# SNC8600A.net
KiCad netlist of a schematic drawn in Altium Designer
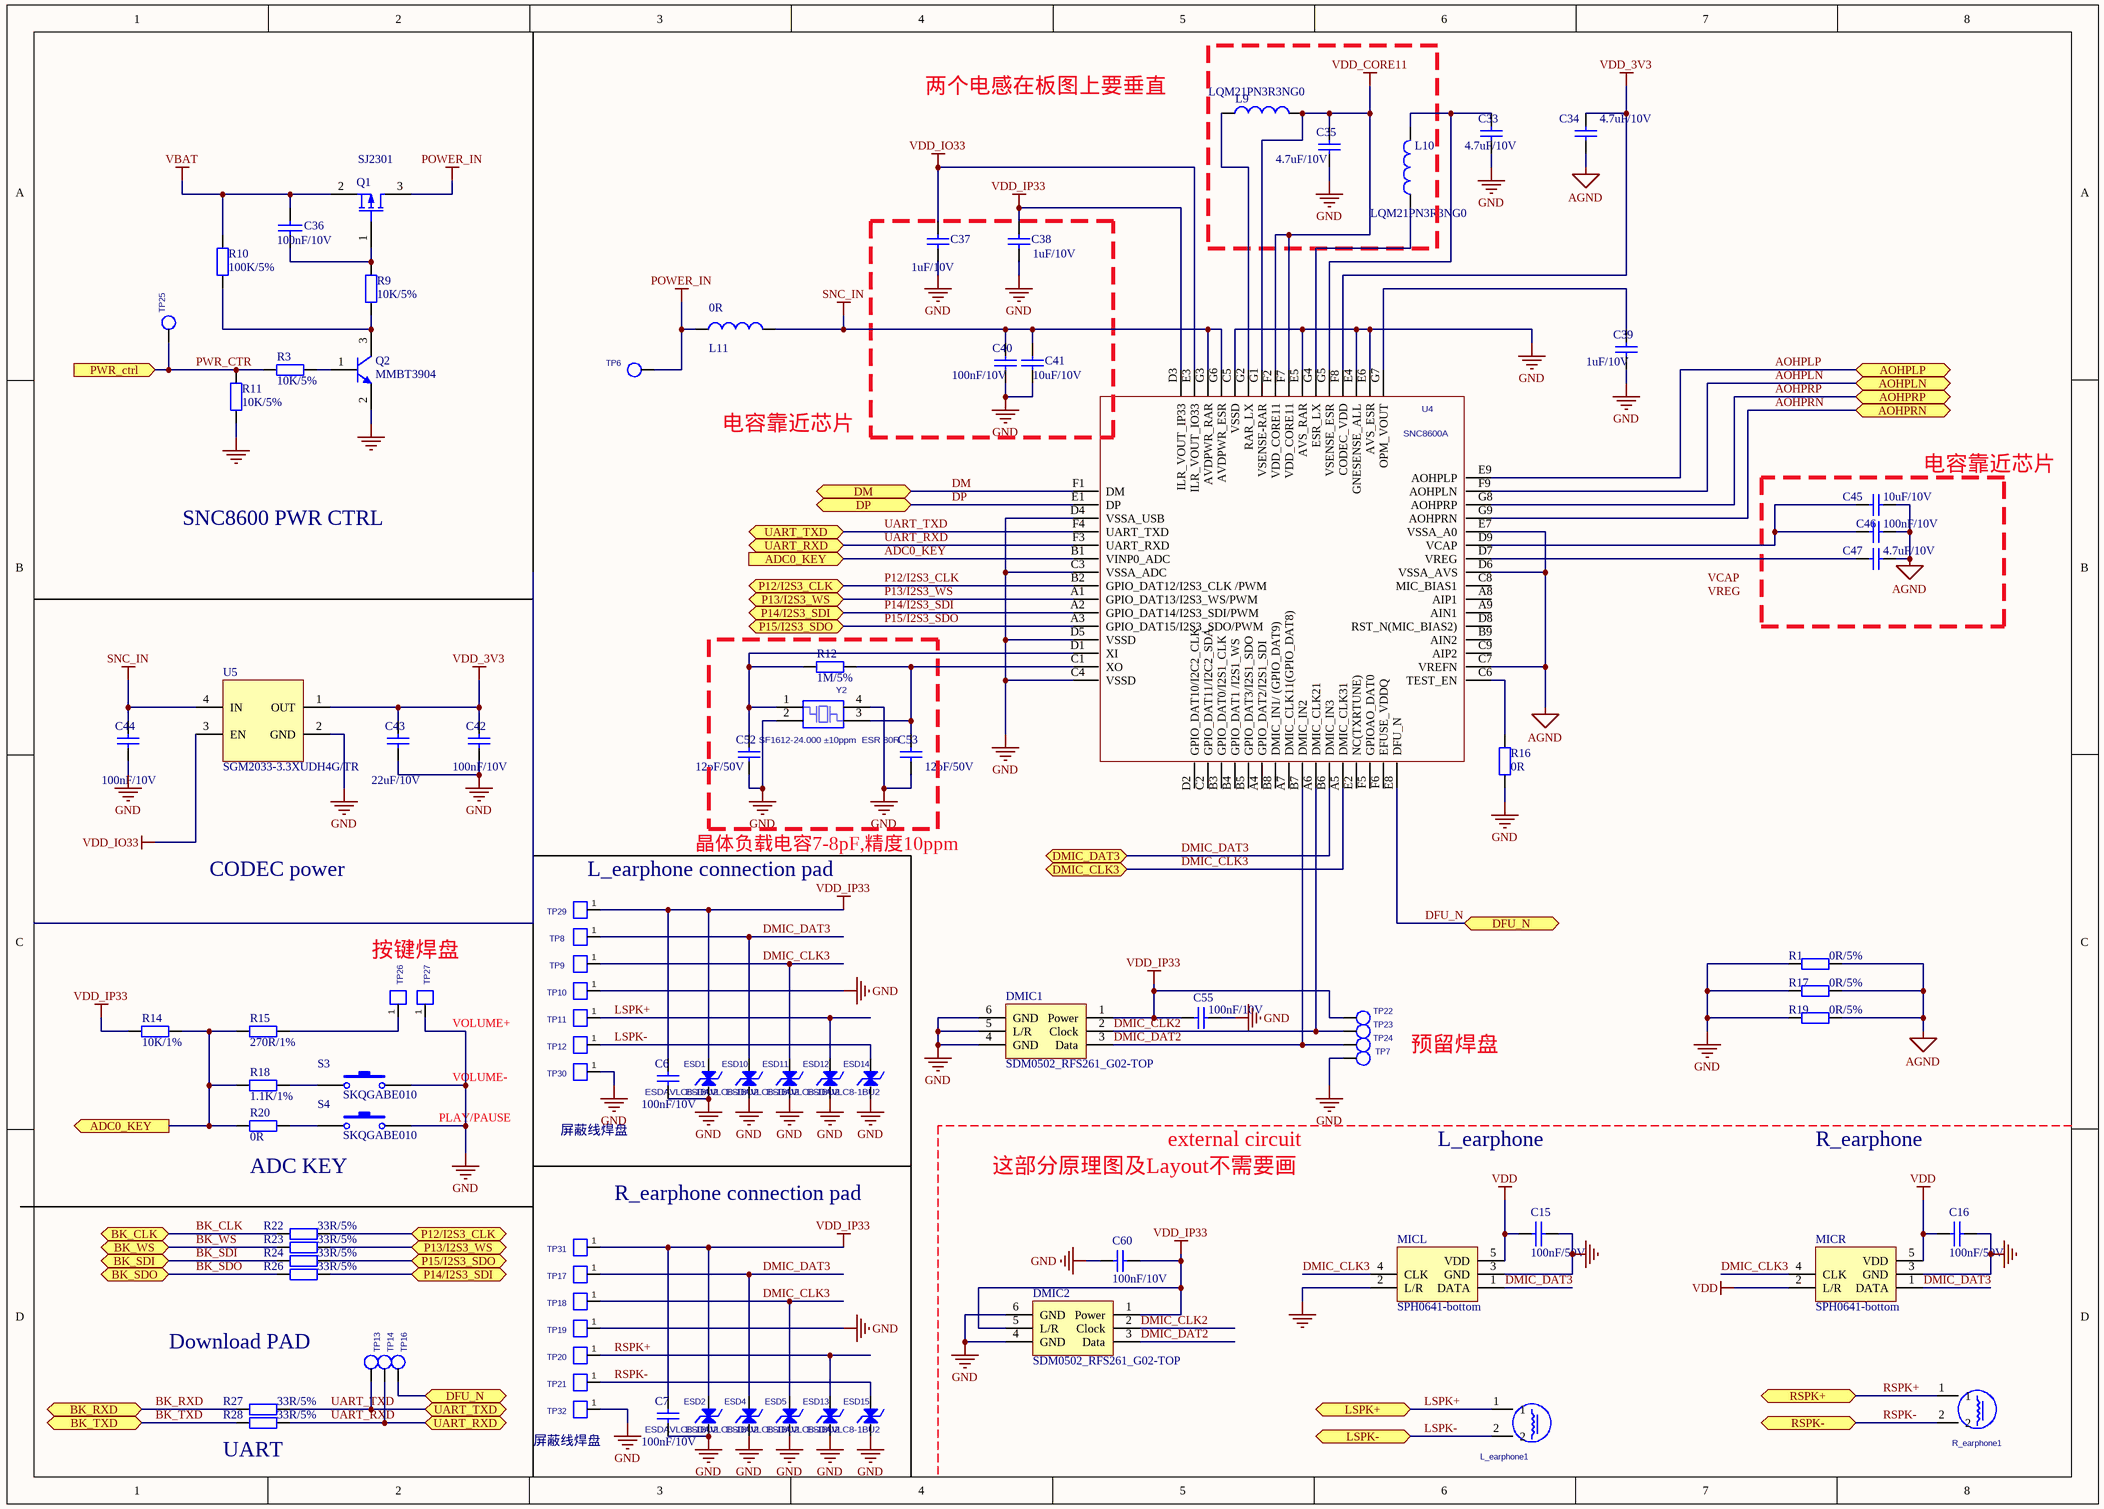
[diagram p0: SNC8600A.SchDoc]

(export (version "E")
  (design (tool "Eeschema 10.0.6"))
  (components
    (comp (ref "C6")
      (value "100nF/10V")
      (footprint "0201")
      (description "Capacitor (Semiconductor SIM Model)")
      (fields (field (name "PUBLISHER") "Altium Limited"))
      (libsource (lib "Miscellaneous Devices") (part "Cap Semi"))
    )
    (comp (ref "C7")
      (value "100nF/10V")
      (footprint "0201")
      (description "Capacitor (Semiconductor SIM Model)")
      (fields (field (name "PUBLISHER") "Altium Limited"))
      (libsource (lib "Miscellaneous Devices") (part "Cap Semi"))
    )
    (comp (ref "C15")
      (value "100nF/50V")
      (footprint "0201")
      (description "Capacitor")
      (libsource (lib "MIC1") (part "CAP-0201"))
    )
    (comp (ref "C16")
      (value "100nF/50V")
      (footprint "0201")
      (description "Capacitor")
      (libsource (lib "MIC1") (part "CAP-0201"))
    )
    (comp (ref "C33")
      (value "4.7uF/10V")
      (footprint "C0402")
      (description "Capacitor (Semiconductor SIM Model)")
      (fields (field (name "PUBLISHER") "Altium Limited"))
      (libsource (lib "Miscellaneous Devices") (part "Cap Semi"))
    )
    (comp (ref "C34")
      (value "4.7uF/10V")
      (footprint "C0402")
      (description "Capacitor (Semiconductor SIM Model)")
      (fields (field (name "PUBLISHER") "Altium Limited"))
      (libsource (lib "Miscellaneous Devices") (part "Cap Semi"))
    )
    (comp (ref "C35")
      (value "4.7uF/10V")
      (footprint "C0402")
      (description "Capacitor (Semiconductor SIM Model)")
      (fields (field (name "PUBLISHER") "Altium Limited"))
      (libsource (lib "Miscellaneous Devices") (part "Cap Semi"))
    )
    (comp (ref "C36")
      (value "100nF/10V")
      (footprint "0201")
      (description "Capacitor")
      (libsource (lib "*") (part "CAP"))
    )
    (comp (ref "C37")
      (value "1uF/10V")
      (footprint "0201")
      (description "Capacitor (Semiconductor SIM Model)")
      (fields (field (name "PUBLISHER") "Altium Limited"))
      (libsource (lib "Miscellaneous Devices") (part "Cap Semi"))
    )
    (comp (ref "C38")
      (value "1uF/10V")
      (footprint "0201")
      (description "Capacitor (Semiconductor SIM Model)")
      (fields (field (name "PUBLISHER") "Altium Limited"))
      (libsource (lib "Miscellaneous Devices") (part "Cap Semi"))
    )
    (comp (ref "C39")
      (value "1uF/10V")
      (footprint "0201")
      (description "Capacitor (Semiconductor SIM Model)")
      (fields (field (name "PUBLISHER") "Altium Limited"))
      (libsource (lib "Miscellaneous Devices") (part "Cap Semi"))
    )
    (comp (ref "C40")
      (value "100nF/10V")
      (footprint "0201")
      (description "Capacitor (Semiconductor SIM Model)")
      (fields (field (name "PUBLISHER") "Altium Limited"))
      (libsource (lib "Miscellaneous Devices") (part "Cap Semi"))
    )
    (comp (ref "C41")
      (value "10uF/10V")
      (footprint "C0402")
      (description "Capacitor (Semiconductor SIM Model)")
      (fields (field (name "PUBLISHER") "Altium Limited"))
      (libsource (lib "Miscellaneous Devices") (part "Cap Semi"))
    )
    (comp (ref "C42")
      (value "100nF/10V")
      (footprint "0201")
      (description "Capacitor (Semiconductor SIM Model)")
      (fields (field (name "PUBLISHER") "Altium Limited"))
      (libsource (lib "Miscellaneous Devices") (part "Cap Semi"))
    )
    (comp (ref "C43")
      (value "22uF/10V")
      (footprint "C0402")
      (description "Capacitor (Semiconductor SIM Model)")
      (fields (field (name "PUBLISHER") "Altium Limited"))
      (libsource (lib "Miscellaneous Devices") (part "Cap Semi"))
    )
    (comp (ref "C44")
      (value "100nF/10V")
      (footprint "0201")
      (description "Capacitor (Semiconductor SIM Model)")
      (fields (field (name "PUBLISHER") "Altium Limited"))
      (libsource (lib "Miscellaneous Devices") (part "Cap Semi"))
    )
    (comp (ref "C45")
      (value "10uF/10V")
      (footprint "C0402")
      (description "Capacitor (Semiconductor SIM Model)")
      (fields (field (name "PUBLISHER") "Altium Limited"))
      (libsource (lib "Miscellaneous Devices") (part "Cap Semi"))
    )
    (comp (ref "C46")
      (value "100nF/10V")
      (footprint "0201")
      (description "Capacitor (Semiconductor SIM Model)")
      (fields (field (name "PUBLISHER") "Altium Limited"))
      (libsource (lib "Miscellaneous Devices") (part "Cap Semi"))
    )
    (comp (ref "C47")
      (value "4.7uF/10V")
      (footprint "C0402")
      (description "Capacitor (Semiconductor SIM Model)")
      (fields (field (name "PUBLISHER") "Altium Limited"))
      (libsource (lib "Miscellaneous Devices") (part "Cap Semi"))
    )
    (comp (ref "C52")
      (value "12pF/50V")
      (footprint "0201")
      (description "Capacitor (Semiconductor SIM Model)")
      (fields (field (name "PUBLISHER") "Altium Limited"))
      (libsource (lib "Miscellaneous Devices") (part "Cap Semi"))
    )
    (comp (ref "C53")
      (value "12pF/50V")
      (footprint "0201")
      (description "Capacitor (Semiconductor SIM Model)")
      (fields (field (name "PUBLISHER") "Altium Limited"))
      (libsource (lib "Miscellaneous Devices") (part "Cap Semi"))
    )
    (comp (ref "C55")
      (value "100nF/10V")
      (footprint "0201")
      (description "Capacitor (Semiconductor SIM Model)")
      (fields (field (name "PUBLISHER") "Altium Limited"))
      (libsource (lib "Miscellaneous Devices") (part "Cap Semi"))
    )
    (comp (ref "C60")
      (value "100nF/10V")
      (footprint "0201")
      (description "Capacitor (Semiconductor SIM Model)")
      (fields (field (name "PUBLISHER") "Altium Limited"))
      (libsource (lib "Miscellaneous Devices") (part "Cap Semi"))
    )
    (comp (ref "DMIC1")
      (value "SDM0502_RFS261_G02-TOP")
      (footprint "3526_TOP")
      (libsource (lib "EVB-SCH-LCD-202003152") (part "3526-TOP"))
    )
    (comp (ref "DMIC2")
      (value "SDM0502_RFS261_G02-TOP")
      (footprint "3526_TOP")
      (libsource (lib "EVB-SCH-LCD-202003152") (part "3526-TOP"))
    )
    (comp (ref "ESD1")
      (value "ESDAVLC8-1BU2")
      (footprint "0201")
      (libsource (lib "EVB-SCH-LCD-202003152") (part "ESD"))
    )
    (comp (ref "ESD2")
      (value "ESDAVLC8-1BU2")
      (footprint "0201")
      (libsource (lib "EVB-SCH-LCD-202003152") (part "ESD"))
    )
    (comp (ref "ESD4")
      (value "ESDAVLC8-1BU2")
      (footprint "0201")
      (libsource (lib "EVB-SCH-LCD-202003152") (part "ESD"))
    )
    (comp (ref "ESD5")
      (value "ESDAVLC8-1BU2")
      (footprint "0201")
      (libsource (lib "EVB-SCH-LCD-202003152") (part "ESD"))
    )
    (comp (ref "ESD10")
      (value "ESDAVLC8-1BU2")
      (footprint "0201")
      (libsource (lib "EVB-SCH-LCD-202003152") (part "ESD"))
    )
    (comp (ref "ESD11")
      (value "ESDAVLC8-1BU2")
      (footprint "0201")
      (libsource (lib "EVB-SCH-LCD-202003152") (part "ESD"))
    )
    (comp (ref "ESD12")
      (value "ESDAVLC8-1BU2")
      (footprint "0201")
      (libsource (lib "EVB-SCH-LCD-202003152") (part "ESD"))
    )
    (comp (ref "ESD13")
      (value "ESDAVLC8-1BU2")
      (footprint "0201")
      (libsource (lib "EVB-SCH-LCD-202003152") (part "ESD"))
    )
    (comp (ref "ESD14")
      (value "ESDAVLC8-1BU2")
      (footprint "0201")
      (libsource (lib "EVB-SCH-LCD-202003152") (part "ESD"))
    )
    (comp (ref "ESD15")
      (value "ESDAVLC8-1BU2")
      (footprint "0201")
      (libsource (lib "EVB-SCH-LCD-202003152") (part "ESD"))
    )
    (comp (ref "L9")
      (value "LQM21PN3R3NG0")
      (footprint "L0805")
      (description "Inductor")
      (fields (field (name "PUBLISHER") "Altium Limited"))
      (libsource (lib "Miscellaneous Devices") (part "Inductor"))
    )
    (comp (ref "L10")
      (value "LQM21PN3R3NG0")
      (footprint "L0805")
      (description "Inductor")
      (fields (field (name "PUBLISHER") "Altium Limited"))
      (libsource (lib "Miscellaneous Devices") (part "Inductor"))
    )
    (comp (ref "L11")
      (value "0R")
      (footprint "0201")
      (description "Inductor")
      (fields (field (name "PUBLISHER") "Altium Limited"))
      (libsource (lib "Miscellaneous Devices") (part "Inductor"))
    )
    (comp (ref "L_earphone1")
      (value "TS1")
      (footprint "2PIN-2.54")
      (libsource (lib "EVB-SCH-LCD-202003152") (part "TS1"))
    )
    (comp (ref "MICL")
      (value "SPH0641-bottom")
      (footprint "SPH_3526")
      (description "MEMS MICPHONE")
      (fields (field (name "PUBLISHER") "Altium Limited"))
      (libsource (lib "MIC1") (part "SPH0641"))
    )
    (comp (ref "MICR")
      (value "SPH0641-bottom")
      (footprint "SPH_3526")
      (description "MEMS MICPHONE")
      (fields (field (name "PUBLISHER") "Altium Limited"))
      (libsource (lib "MIC1") (part "SPH0641"))
    )
    (comp (ref "Q1")
      (value "SJ2301")
      (footprint "SOT23_3407")
      (description "P-Channel MOSFET")
      (fields (field (name "PUBLISHER") "Altium Limited"))
      (libsource (lib "Miscellaneous Devices") (part "MOSFET-P"))
    )
    (comp (ref "Q2")
      (value "MMBT3904")
      (footprint "SOT23")
      (description "NPN General Purpose Amplifier")
      (fields (field (name "PUBLISHER") "Altium Limited"))
      (libsource (lib "Miscellaneous Devices") (part "2N3904"))
    )
    (comp (ref "R1")
      (value "0R/5%")
      (footprint "0201")
      (description "Resistor")
      (fields (field (name "PUBLISHER") "Altium Limited"))
      (libsource (lib "Miscellaneous Devices") (part "Res2"))
    )
    (comp (ref "R3")
      (value "10K/5%")
      (footprint "0201")
      (description "Resistor")
      (fields (field (name "PUBLISHER") "Altium Limited"))
      (libsource (lib "") (part "Res2_2"))
    )
    (comp (ref "R9")
      (value "10K/5%")
      (footprint "0201")
      (description "Resistor")
      (fields (field (name "PUBLISHER") "Altium Limited"))
      (libsource (lib "") (part "Res2_1"))
    )
    (comp (ref "R10")
      (value "100K/5%")
      (footprint "0201")
      (description "Resistor")
      (fields (field (name "PUBLISHER") "Altium Limited"))
      (libsource (lib "") (part "Res2_1"))
    )
    (comp (ref "R11")
      (value "10K/5%")
      (footprint "0201")
      (description "Resistor")
      (fields (field (name "PUBLISHER") "Altium Limited"))
      (libsource (lib "") (part "Res2_1"))
    )
    (comp (ref "R12")
      (value "1M/5%")
      (footprint "0201")
      (description "Resistor")
      (fields (field (name "PUBLISHER") "Altium Limited"))
      (libsource (lib "Miscellaneous Devices") (part "Res2"))
    )
    (comp (ref "R14")
      (value "10K/1%")
      (footprint "0201")
      (description "Resistor")
      (fields (field (name "PUBLISHER") "Altium Limited"))
      (libsource (lib "Miscellaneous Devices") (part "Res2"))
    )
    (comp (ref "R15")
      (value "270R/1%")
      (footprint "0201")
      (description "Resistor")
      (fields (field (name "PUBLISHER") "Altium Limited"))
      (libsource (lib "Miscellaneous Devices") (part "Res2"))
    )
    (comp (ref "R16")
      (value "0R")
      (footprint "0201")
      (description "Resistor")
      (fields (field (name "PUBLISHER") "Altium Limited"))
      (libsource (lib "") (part "Res2_1"))
    )
    (comp (ref "R17")
      (value "0R/5%")
      (footprint "0201")
      (description "Resistor")
      (fields (field (name "PUBLISHER") "Altium Limited"))
      (libsource (lib "Miscellaneous Devices") (part "Res2"))
    )
    (comp (ref "R18")
      (value "1.1K/1%")
      (footprint "0201")
      (description "Resistor")
      (fields (field (name "PUBLISHER") "Altium Limited"))
      (libsource (lib "Miscellaneous Devices") (part "Res2"))
    )
    (comp (ref "R19")
      (value "0R/5%")
      (footprint "0201")
      (description "Resistor")
      (fields (field (name "PUBLISHER") "Altium Limited"))
      (libsource (lib "Miscellaneous Devices") (part "Res2"))
    )
    (comp (ref "R20")
      (value "0R")
      (footprint "0201")
      (description "Resistor")
      (fields (field (name "PUBLISHER") "Altium Limited"))
      (libsource (lib "Miscellaneous Devices") (part "Res2"))
    )
    (comp (ref "R22")
      (value "33R/5%")
      (footprint "0201")
      (description "Resistor")
      (fields (field (name "PUBLISHER") "Altium Limited"))
      (libsource (lib "Miscellaneous Devices") (part "Res2"))
    )
    (comp (ref "R23")
      (value "33R/5%")
      (footprint "0201")
      (description "Resistor")
      (fields (field (name "PUBLISHER") "Altium Limited"))
      (libsource (lib "Miscellaneous Devices") (part "Res2"))
    )
    (comp (ref "R24")
      (value "33R/5%")
      (footprint "0201")
      (description "Resistor")
      (fields (field (name "PUBLISHER") "Altium Limited"))
      (libsource (lib "Miscellaneous Devices") (part "Res2"))
    )
    (comp (ref "R26")
      (value "33R/5%")
      (footprint "0201")
      (description "Resistor")
      (fields (field (name "PUBLISHER") "Altium Limited"))
      (libsource (lib "Miscellaneous Devices") (part "Res2"))
    )
    (comp (ref "R27")
      (value "33R/5%")
      (footprint "0201")
      (description "Resistor")
      (fields (field (name "PUBLISHER") "Altium Limited"))
      (libsource (lib "Miscellaneous Devices") (part "Res2"))
    )
    (comp (ref "R28")
      (value "33R/5%")
      (footprint "0201")
      (description "Resistor")
      (fields (field (name "PUBLISHER") "Altium Limited"))
      (libsource (lib "Miscellaneous Devices") (part "Res2"))
    )
    (comp (ref "R_earphone1")
      (value "TS1")
      (footprint "2PIN-2.54")
      (libsource (lib "EVB-SCH-LCD-202003152") (part "TS1"))
    )
    (comp (ref "S3")
      (value "SKQGABE010")
      (footprint "TD-302060")
      (description "Switch")
      (fields (field (name "PUBLISHER") "Altium Limited"))
      (libsource (lib "Miscellaneous Devices") (part "SW-PB"))
    )
    (comp (ref "S4")
      (value "SKQGABE010")
      (footprint "TD-302060")
      (description "Switch")
      (fields (field (name "PUBLISHER") "Altium Limited"))
      (libsource (lib "Miscellaneous Devices") (part "SW-PB"))
    )
    (comp (ref "TP6")
      (value "TP1")
      (footprint "TP1-1MM")
      (libsource (lib "EVB-SCH-LCD-202003152") (part "TP1"))
    )
    (comp (ref "TP7")
      (value "TP1")
      (footprint "TP1-1MM")
      (libsource (lib "EVB-SCH-LCD-202003152") (part "TP1"))
    )
    (comp (ref "TP8")
      (value "TP")
      (footprint "TP1-1MM")
      (libsource (lib "EVB-SCH-LCD-202003152") (part "TP"))
    )
    (comp (ref "TP9")
      (value "TP")
      (footprint "TP1-1MM")
      (libsource (lib "EVB-SCH-LCD-202003152") (part "TP"))
    )
    (comp (ref "TP10")
      (value "TP")
      (footprint "TP1-1MM")
      (libsource (lib "EVB-SCH-LCD-202003152") (part "TP"))
    )
    (comp (ref "TP11")
      (value "TP")
      (footprint "TP1-1MM")
      (libsource (lib "EVB-SCH-LCD-202003152") (part "TP"))
    )
    (comp (ref "TP12")
      (value "TP")
      (footprint "TP1-1MM")
      (libsource (lib "EVB-SCH-LCD-202003152") (part "TP"))
    )
    (comp (ref "TP13")
      (value "TP1")
      (footprint "TP1-1MM")
      (libsource (lib "EVB-SCH-LCD-202003152") (part "TP1"))
    )
    (comp (ref "TP14")
      (value "TP1")
      (footprint "TP1-1MM")
      (libsource (lib "EVB-SCH-LCD-202003152") (part "TP1"))
    )
    (comp (ref "TP16")
      (value "TP1")
      (footprint "TP1-1MM")
      (libsource (lib "EVB-SCH-LCD-202003152") (part "TP1"))
    )
    (comp (ref "TP17")
      (value "TP")
      (footprint "TP1-1MM")
      (libsource (lib "EVB-SCH-LCD-202003152") (part "TP"))
    )
    (comp (ref "TP18")
      (value "TP")
      (footprint "TP1-1MM")
      (libsource (lib "EVB-SCH-LCD-202003152") (part "TP"))
    )
    (comp (ref "TP19")
      (value "TP")
      (footprint "TP1-1MM")
      (libsource (lib "EVB-SCH-LCD-202003152") (part "TP"))
    )
    (comp (ref "TP20")
      (value "TP")
      (footprint "TP1-1MM")
      (libsource (lib "EVB-SCH-LCD-202003152") (part "TP"))
    )
    (comp (ref "TP21")
      (value "TP")
      (footprint "TP1-1MM")
      (libsource (lib "EVB-SCH-LCD-202003152") (part "TP"))
    )
    (comp (ref "TP22")
      (value "TP1")
      (footprint "TP1-1MM")
      (libsource (lib "EVB-SCH-LCD-202003152") (part "TP1"))
    )
    (comp (ref "TP23")
      (value "TP1")
      (footprint "TP1-1MM")
      (libsource (lib "EVB-SCH-LCD-202003152") (part "TP1"))
    )
    (comp (ref "TP24")
      (value "TP1")
      (footprint "TP1-1MM")
      (libsource (lib "EVB-SCH-LCD-202003152") (part "TP1"))
    )
    (comp (ref "TP25")
      (value "TP1")
      (footprint "TP1-1MM")
      (libsource (lib "EVB-SCH-LCD-202003152") (part "TP1"))
    )
    (comp (ref "TP26")
      (value "TP")
      (footprint "TP1-1MM")
      (libsource (lib "EVB-SCH-LCD-202003152") (part "TP"))
    )
    (comp (ref "TP27")
      (value "TP")
      (footprint "TP1-1MM")
      (libsource (lib "EVB-SCH-LCD-202003152") (part "TP"))
    )
    (comp (ref "TP29")
      (value "TP")
      (footprint "TP1-1MM")
      (libsource (lib "EVB-SCH-LCD-202003152") (part "TP"))
    )
    (comp (ref "TP30")
      (value "TP")
      (footprint "TP1-1MM")
      (libsource (lib "EVB-SCH-LCD-202003152") (part "TP"))
    )
    (comp (ref "TP31")
      (value "TP")
      (footprint "TP1-1MM")
      (libsource (lib "EVB-SCH-LCD-202003152") (part "TP"))
    )
    (comp (ref "TP32")
      (value "TP")
      (footprint "TP1-1MM")
      (libsource (lib "EVB-SCH-LCD-202003152") (part "TP"))
    )
    (comp (ref "U4")
      (value "SNC8600A")
      (footprint "BGA63C50P9X7_500X350X100")
      (libsource (lib "EVB-SCH-LCD-202003152") (part "SNC8600A"))
    )
    (comp (ref "U5")
      (value "SGM2033-3.3XUDH4G/TR")
      (footprint "UTDFN-1X1-4AL")
      (libsource (lib "EVB-SCH-LCD-202003152") (part "SGM2033"))
    )
    (comp (ref "Y2")
      (value "SF1612-24.000 ±10ppm  ESR 80R")
      (footprint "SF1612")
      (fields (field (name "Comment") "SF1612"))
      (libsource (lib "EVB-SCH-LCD-202003152") (part "SF1612"))
    )
  )
  (nets
    (net (code "1") (name "/ADC0_KEY") (class "Default")
      (node (ref "R14") (pin "1") (pinfunction "1_1") (pintype "passive"))
      (node (ref "R15") (pin "2") (pinfunction "2_2") (pintype "passive"))
      (node (ref "R18") (pin "2") (pinfunction "2_2") (pintype "passive"))
      (node (ref "R20") (pin "2") (pinfunction "2_2") (pintype "passive"))
      (node (ref "U4") (pin "B1") (pinfunction "VINP0_ADC_B1") (pintype "passive"))
    )
    (net (code "2") (name "/AOHPLN") (class "Default")
      (node (ref "U4") (pin "F9") (pinfunction "AOHPLN_F9") (pintype "passive"))
    )
    (net (code "3") (name "/AOHPLP") (class "Default")
      (node (ref "U4") (pin "E9") (pinfunction "AOHPLP_E9") (pintype "passive"))
    )
    (net (code "4") (name "/AOHPRN") (class "Default")
      (node (ref "U4") (pin "G9") (pinfunction "AOHPRN_G9") (pintype "passive"))
    )
    (net (code "5") (name "/AOHPRP") (class "Default")
      (node (ref "U4") (pin "G8") (pinfunction "AOHPRP_G8") (pintype "passive"))
    )
    (net (code "6") (name "/BK_CLK") (class "Default")
      (node (ref "R22") (pin "2") (pinfunction "2_2") (pintype "passive"))
    )
    (net (code "7") (name "/BK_RXD") (class "Default")
      (node (ref "R27") (pin "2") (pinfunction "2_2") (pintype "passive"))
    )
    (net (code "8") (name "/BK_SDI") (class "Default")
      (node (ref "R24") (pin "2") (pinfunction "2_2") (pintype "passive"))
    )
    (net (code "9") (name "/BK_SDO") (class "Default")
      (node (ref "R26") (pin "2") (pinfunction "2_2") (pintype "passive"))
    )
    (net (code "10") (name "/BK_TXD") (class "Default")
      (node (ref "R28") (pin "2") (pinfunction "2_2") (pintype "passive"))
    )
    (net (code "11") (name "/BK_WS") (class "Default")
      (node (ref "R23") (pin "2") (pinfunction "2_2") (pintype "passive"))
    )
    (net (code "12") (name "/DFU_N") (class "Default")
      (node (ref "TP16") (pin "1") (pinfunction "1_1") (pintype "passive"))
      (node (ref "U4") (pin "E8") (pinfunction "DFU_N_E8") (pintype "passive"))
    )
    (net (code "13") (name "/DM") (class "Default")
      (node (ref "U4") (pin "F1") (pinfunction "DM_F1") (pintype "passive"))
    )
    (net (code "14") (name "/DMIC_CLK2") (class "Default")
      (node (ref "DMIC1") (pin "2") (pinfunction "Clock_2") (pintype "passive"))
      (node (ref "DMIC2") (pin "2") (pinfunction "Clock_2") (pintype "passive"))
      (node (ref "TP23") (pin "1") (pinfunction "1_1") (pintype "passive"))
      (node (ref "U4") (pin "A6") (pinfunction "DMIC_CLK21_A6") (pintype "passive"))
    )
    (net (code "15") (name "/DMIC_CLK3") (class "Default")
      (node (ref "ESD11") (pin "1") (pinfunction "1_1") (pintype "passive"))
      (node (ref "ESD5") (pin "1") (pinfunction "1_1") (pintype "passive"))
      (node (ref "MICL") (pin "4") (pinfunction "CLK_4") (pintype "power_in"))
      (node (ref "MICR") (pin "4") (pinfunction "CLK_4") (pintype "power_in"))
      (node (ref "TP18") (pin "1") (pinfunction "1_1") (pintype "passive"))
      (node (ref "TP9") (pin "1") (pinfunction "1_1") (pintype "passive"))
      (node (ref "U4") (pin "A5") (pinfunction "DMIC_CLK31_A5") (pintype "passive"))
    )
    (net (code "16") (name "/DMIC_DAT2") (class "Default")
      (node (ref "DMIC1") (pin "3") (pinfunction "Data_3") (pintype "passive"))
      (node (ref "DMIC2") (pin "3") (pinfunction "Data_3") (pintype "passive"))
      (node (ref "TP24") (pin "1") (pinfunction "1_1") (pintype "passive"))
      (node (ref "U4") (pin "B7") (pinfunction "DMIC_IN2_B7") (pintype "passive"))
    )
    (net (code "17") (name "/DMIC_DAT3") (class "Default")
      (node (ref "ESD10") (pin "1") (pinfunction "1_1") (pintype "passive"))
      (node (ref "ESD4") (pin "1") (pinfunction "1_1") (pintype "passive"))
      (node (ref "MICL") (pin "1") (pinfunction "DATA_1") (pintype "passive"))
      (node (ref "MICR") (pin "1") (pinfunction "DATA_1") (pintype "passive"))
      (node (ref "TP17") (pin "1") (pinfunction "1_1") (pintype "passive"))
      (node (ref "TP8") (pin "1") (pinfunction "1_1") (pintype "passive"))
      (node (ref "U4") (pin "B6") (pinfunction "DMIC_IN3_B6") (pintype "passive"))
    )
    (net (code "18") (name "/DP") (class "Default")
      (node (ref "U4") (pin "E1") (pinfunction "DP_E1") (pintype "passive"))
    )
    (net (code "19") (name "/LSPK+") (class "Default")
      (node (ref "ESD12") (pin "1") (pinfunction "1_1") (pintype "passive"))
      (node (ref "L_earphone1") (pin "1") (pinfunction "1_1") (pintype "passive"))
      (node (ref "TP11") (pin "1") (pinfunction "1_1") (pintype "passive"))
    )
    (net (code "20") (name "/LSPK-") (class "Default")
      (node (ref "ESD14") (pin "1") (pinfunction "1_1") (pintype "passive"))
      (node (ref "L_earphone1") (pin "2") (pinfunction "2_2") (pintype "passive"))
      (node (ref "TP12") (pin "1") (pinfunction "1_1") (pintype "passive"))
    )
    (net (code "21") (name "/P12{slash}I2S3_CLK") (class "Default")
      (node (ref "R22") (pin "1") (pinfunction "1_1") (pintype "passive"))
      (node (ref "U4") (pin "B2") (pinfunction "GPIO_DAT12/I2S3_CLK_/PWM_B2") (pintype "passive"))
    )
    (net (code "22") (name "/P13{slash}I2S3_WS") (class "Default")
      (node (ref "R23") (pin "1") (pinfunction "1_1") (pintype "passive"))
      (node (ref "U4") (pin "A1") (pinfunction "GPIO_DAT13/I2S3_WS/PWM_A1") (pintype "passive"))
    )
    (net (code "23") (name "/P14{slash}I2S3_SDI") (class "Default")
      (node (ref "R26") (pin "1") (pinfunction "1_1") (pintype "passive"))
      (node (ref "U4") (pin "A2") (pinfunction "GPIO_DAT14/I2S3_SDI/PWM_A2") (pintype "passive"))
    )
    (net (code "24") (name "/P15{slash}I2S3_SDO") (class "Default")
      (node (ref "R24") (pin "1") (pinfunction "1_1") (pintype "passive"))
      (node (ref "U4") (pin "A3") (pinfunction "GPIO_DAT15/I2S3_SDO/PWM_A3") (pintype "passive"))
    )
    (net (code "25") (name "/PWR_CTR") (class "Default")
      (node (ref "R11") (pin "1") (pinfunction "1_1") (pintype "passive"))
      (node (ref "R3") (pin "1") (pinfunction "1_1") (pintype "passive"))
      (node (ref "TP25") (pin "1") (pinfunction "1_1") (pintype "passive"))
    )
    (net (code "26") (name "/RSPK+") (class "Default")
      (node (ref "ESD13") (pin "1") (pinfunction "1_1") (pintype "passive"))
      (node (ref "R_earphone1") (pin "1") (pinfunction "1_1") (pintype "passive"))
      (node (ref "TP20") (pin "1") (pinfunction "1_1") (pintype "passive"))
    )
    (net (code "27") (name "/RSPK-") (class "Default")
      (node (ref "ESD15") (pin "1") (pinfunction "1_1") (pintype "passive"))
      (node (ref "R_earphone1") (pin "2") (pinfunction "2_2") (pintype "passive"))
      (node (ref "TP21") (pin "1") (pinfunction "1_1") (pintype "passive"))
    )
    (net (code "28") (name "/UART_RXD") (class "Default")
      (node (ref "R28") (pin "1") (pinfunction "1_1") (pintype "passive"))
      (node (ref "TP14") (pin "1") (pinfunction "1_1") (pintype "passive"))
      (node (ref "U4") (pin "F3") (pinfunction "UART_RXD_F3") (pintype "passive"))
    )
    (net (code "29") (name "/UART_TXD") (class "Default")
      (node (ref "R27") (pin "1") (pinfunction "1_1") (pintype "passive"))
      (node (ref "TP13") (pin "1") (pinfunction "1_1") (pintype "passive"))
      (node (ref "U4") (pin "F4") (pinfunction "UART_TXD_F4") (pintype "passive"))
    )
    (net (code "32") (name "AGND") (class "Default")
      (node (ref "C34") (pin "1") (pinfunction "1_1") (pintype "passive"))
      (node (ref "C45") (pin "1") (pinfunction "1_1") (pintype "passive"))
      (node (ref "C46") (pin "1") (pinfunction "1_1") (pintype "passive"))
      (node (ref "C47") (pin "1") (pinfunction "1_1") (pintype "passive"))
      (node (ref "R1") (pin "1") (pinfunction "1_1") (pintype "passive"))
      (node (ref "R17") (pin "1") (pinfunction "1_1") (pintype "passive"))
      (node (ref "R19") (pin "1") (pinfunction "1_1") (pintype "passive"))
      (node (ref "U4") (pin "C7") (pinfunction "VREFN_C7") (pintype "passive"))
      (node (ref "U4") (pin "D6") (pinfunction "VSSA_AVS_D6") (pintype "passive"))
      (node (ref "U4") (pin "E7") (pinfunction "VSSA_A0_E7") (pintype "passive"))
    )
    (net (code "33") (name "GND") (class "Default")
      (node (ref "C15") (pin "1") (pinfunction "1_1") (pintype "passive"))
      (node (ref "C16") (pin "1") (pinfunction "1_1") (pintype "passive"))
      (node (ref "C33") (pin "1") (pinfunction "1_1") (pintype "passive"))
      (node (ref "C35") (pin "1") (pinfunction "1_1") (pintype "passive"))
      (node (ref "C37") (pin "1") (pinfunction "1_1") (pintype "passive"))
      (node (ref "C38") (pin "1") (pinfunction "1_1") (pintype "passive"))
      (node (ref "C39") (pin "1") (pinfunction "1_1") (pintype "passive"))
      (node (ref "C40") (pin "1") (pinfunction "1_1") (pintype "passive"))
      (node (ref "C41") (pin "1") (pinfunction "1_1") (pintype "passive"))
      (node (ref "C42") (pin "1") (pinfunction "1_1") (pintype "passive"))
      (node (ref "C43") (pin "1") (pinfunction "1_1") (pintype "passive"))
      (node (ref "C44") (pin "1") (pinfunction "1_1") (pintype "passive"))
      (node (ref "C52") (pin "1") (pinfunction "1_1") (pintype "passive"))
      (node (ref "C53") (pin "1") (pinfunction "1_1") (pintype "passive"))
      (node (ref "C55") (pin "1") (pinfunction "1_1") (pintype "passive"))
      (node (ref "C6") (pin "1") (pinfunction "1_1") (pintype "passive"))
      (node (ref "C60") (pin "1") (pinfunction "1_1") (pintype "passive"))
      (node (ref "C7") (pin "1") (pinfunction "1_1") (pintype "passive"))
      (node (ref "DMIC1") (pin "4") (pinfunction "GND_4") (pintype "passive"))
      (node (ref "DMIC1") (pin "5") (pinfunction "L/R_5") (pintype "passive"))
      (node (ref "DMIC1") (pin "6") (pinfunction "GND_6") (pintype "passive"))
      (node (ref "DMIC2") (pin "4") (pinfunction "GND_4") (pintype "passive"))
      (node (ref "DMIC2") (pin "6") (pinfunction "GND_6") (pintype "passive"))
      (node (ref "ESD1") (pin "2") (pinfunction "2_2") (pintype "passive"))
      (node (ref "ESD10") (pin "2") (pinfunction "2_2") (pintype "passive"))
      (node (ref "ESD11") (pin "2") (pinfunction "2_2") (pintype "passive"))
      (node (ref "ESD12") (pin "2") (pinfunction "2_2") (pintype "passive"))
      (node (ref "ESD13") (pin "2") (pinfunction "2_2") (pintype "passive"))
      (node (ref "ESD14") (pin "2") (pinfunction "2_2") (pintype "passive"))
      (node (ref "ESD15") (pin "2") (pinfunction "2_2") (pintype "passive"))
      (node (ref "ESD2") (pin "2") (pinfunction "2_2") (pintype "passive"))
      (node (ref "ESD4") (pin "2") (pinfunction "2_2") (pintype "passive"))
      (node (ref "ESD5") (pin "2") (pinfunction "2_2") (pintype "passive"))
      (node (ref "MICL") (pin "2") (pinfunction "L/R_2") (pintype "passive"))
      (node (ref "MICL") (pin "3") (pinfunction "GND_3") (pintype "power_in"))
      (node (ref "MICR") (pin "3") (pinfunction "GND_3") (pintype "power_in"))
      (node (ref "Q2") (pin "2") (pinfunction "E_2") (pintype "passive"))
      (node (ref "R1") (pin "2") (pinfunction "2_2") (pintype "passive"))
      (node (ref "R11") (pin "2") (pinfunction "2_2") (pintype "passive"))
      (node (ref "R16") (pin "2") (pinfunction "2_2") (pintype "passive"))
      (node (ref "R17") (pin "2") (pinfunction "2_2") (pintype "passive"))
      (node (ref "R19") (pin "2") (pinfunction "2_2") (pintype "passive"))
      (node (ref "S3") (pin "1") (pinfunction "1_1") (pintype "passive"))
      (node (ref "S4") (pin "1") (pinfunction "1_1") (pintype "passive"))
      (node (ref "TP10") (pin "1") (pinfunction "1_1") (pintype "passive"))
      (node (ref "TP19") (pin "1") (pinfunction "1_1") (pintype "passive"))
      (node (ref "TP27") (pin "1") (pinfunction "1_1") (pintype "passive"))
      (node (ref "TP30") (pin "1") (pinfunction "1_1") (pintype "passive"))
      (node (ref "TP32") (pin "1") (pinfunction "1_1") (pintype "passive"))
      (node (ref "TP7") (pin "1") (pinfunction "1_1") (pintype "passive"))
      (node (ref "U4") (pin "C3") (pinfunction "VSSA_ADC_C3") (pintype "passive"))
      (node (ref "U4") (pin "C4") (pinfunction "VSSD_C4") (pintype "passive"))
      (node (ref "U4") (pin "C5") (pinfunction "VSSD_C5") (pintype "passive"))
      (node (ref "U4") (pin "D4") (pinfunction "VSSA_USB_D4") (pintype "passive"))
      (node (ref "U4") (pin "D5") (pinfunction "VSSD_D5") (pintype "passive"))
      (node (ref "U4") (pin "E4") (pinfunction "GNESENSE_ALL_E4") (pintype "passive"))
      (node (ref "U4") (pin "E5") (pinfunction "AVS_RAR_E5") (pintype "passive"))
      (node (ref "U4") (pin "E6") (pinfunction "AVS_ESR_E6") (pintype "passive"))
      (node (ref "U5") (pin "2") (pinfunction "GND_2") (pintype "passive"))
      (node (ref "Y2") (pin "2") (pinfunction "2_2") (pintype "passive"))
      (node (ref "Y2") (pin "4") (pinfunction "4_4") (pintype "passive"))
    )
    (net (code "34") (name "Net-(Q1-G)") (class "Default")
      (node (ref "C36") (pin "1") (pinfunction "1_1") (pintype "passive"))
      (node (ref "Q1") (pin "1") (pinfunction "G_1") (pintype "passive"))
      (node (ref "R9") (pin "1") (pinfunction "1_1") (pintype "passive"))
    )
    (net (code "35") (name "Net-(Q2-B)") (class "Default")
      (node (ref "Q2") (pin "1") (pinfunction "B_1") (pintype "passive"))
      (node (ref "R3") (pin "2") (pinfunction "2_2") (pintype "passive"))
    )
    (net (code "36") (name "Net-(Q2-C)") (class "Default")
      (node (ref "Q2") (pin "3") (pinfunction "C_3") (pintype "passive"))
      (node (ref "R10") (pin "2") (pinfunction "2_2") (pintype "passive"))
      (node (ref "R9") (pin "2") (pinfunction "2_2") (pintype "passive"))
    )
    (net (code "37") (name "Net-(R15-Pad1)") (class "Default")
      (node (ref "R15") (pin "1") (pinfunction "1_1") (pintype "passive"))
      (node (ref "TP26") (pin "1") (pinfunction "1_1") (pintype "passive"))
    )
    (net (code "38") (name "Net-(R18-Pad1)") (class "Default")
      (node (ref "R18") (pin "1") (pinfunction "1_1") (pintype "passive"))
      (node (ref "S3") (pin "2") (pinfunction "2_2") (pintype "passive"))
    )
    (net (code "39") (name "Net-(R20-Pad1)") (class "Default")
      (node (ref "R20") (pin "1") (pinfunction "1_1") (pintype "passive"))
      (node (ref "S4") (pin "2") (pinfunction "2_2") (pintype "passive"))
    )
    (net (code "40") (name "Net-(U4-ESR_LX)") (class "Default")
      (node (ref "L10") (pin "1") (pinfunction "1_1") (pintype "passive"))
      (node (ref "U4") (pin "G4") (pinfunction "ESR_LX_G4") (pintype "passive"))
    )
    (net (code "41") (name "Net-(U4-OPM_VOUT)") (class "Default")
      (node (ref "C39") (pin "2") (pinfunction "2_2") (pintype "passive"))
      (node (ref "U4") (pin "G7") (pinfunction "OPM_VOUT_G7") (pintype "passive"))
    )
    (net (code "42") (name "Net-(U4-RAR_LX)") (class "Default")
      (node (ref "L9") (pin "1") (pinfunction "1_1") (pintype "passive"))
      (node (ref "U4") (pin "G2") (pinfunction "RAR_LX_G2") (pintype "passive"))
    )
    (net (code "43") (name "Net-(U4-TEST_EN)") (class "Default")
      (node (ref "R16") (pin "1") (pinfunction "1_1") (pintype "passive"))
      (node (ref "U4") (pin "C6") (pinfunction "TEST_EN_C6") (pintype "passive"))
    )
    (net (code "44") (name "Net-(U4-VCAP)") (class "Default")
      (node (ref "C45") (pin "2") (pinfunction "2_2") (pintype "passive"))
      (node (ref "C46") (pin "2") (pinfunction "2_2") (pintype "passive"))
      (node (ref "U4") (pin "D9") (pinfunction "VCAP_D9") (pintype "passive"))
    )
    (net (code "45") (name "Net-(U4-VREG)") (class "Default")
      (node (ref "C47") (pin "2") (pinfunction "2_2") (pintype "passive"))
      (node (ref "U4") (pin "D7") (pinfunction "VREG_D7") (pintype "passive"))
    )
    (net (code "46") (name "Net-(U4-VSENSE_ESR)") (class "Default")
      (node (ref "C33") (pin "2") (pinfunction "2_2") (pintype "passive"))
      (node (ref "L10") (pin "2") (pinfunction "2_2") (pintype "passive"))
      (node (ref "U4") (pin "G5") (pinfunction "VSENSE_ESR_G5") (pintype "passive"))
    )
    (net (code "47") (name "Net-(U4-XI)") (class "Default")
      (node (ref "C52") (pin "2") (pinfunction "2_2") (pintype "passive"))
      (node (ref "R12") (pin "2") (pinfunction "2_2") (pintype "passive"))
      (node (ref "U4") (pin "D1") (pinfunction "XI_D1") (pintype "passive"))
      (node (ref "Y2") (pin "1") (pinfunction "1_1") (pintype "passive"))
    )
    (net (code "48") (name "Net-(U4-XO)") (class "Default")
      (node (ref "C53") (pin "2") (pinfunction "2_2") (pintype "passive"))
      (node (ref "R12") (pin "1") (pinfunction "1_1") (pintype "passive"))
      (node (ref "U4") (pin "C1") (pinfunction "XO_C1") (pintype "passive"))
      (node (ref "Y2") (pin "3") (pinfunction "3_3") (pintype "passive"))
    )
    (net (code "49") (name "POWER_IN") (class "Default")
      (node (ref "L11") (pin "1") (pinfunction "1_1") (pintype "passive"))
      (node (ref "Q1") (pin "3") (pinfunction "D_3") (pintype "passive"))
      (node (ref "TP6") (pin "1") (pinfunction "1_1") (pintype "passive"))
    )
    (net (code "50") (name "SNC_IN") (class "Default")
      (node (ref "C40") (pin "2") (pinfunction "2_2") (pintype "passive"))
      (node (ref "C41") (pin "2") (pinfunction "2_2") (pintype "passive"))
      (node (ref "C44") (pin "2") (pinfunction "2_2") (pintype "passive"))
      (node (ref "L11") (pin "2") (pinfunction "2_2") (pintype "passive"))
      (node (ref "U4") (pin "G3") (pinfunction "AVDPWR_RAR_G3") (pintype "passive"))
      (node (ref "U4") (pin "G6") (pinfunction "AVDPWR_ESR_G6") (pintype "passive"))
      (node (ref "U5") (pin "4") (pinfunction "IN_4") (pintype "passive"))
    )
    (net (code "51") (name "VBAT") (class "Default")
      (node (ref "C36") (pin "2") (pinfunction "2_2") (pintype "passive"))
      (node (ref "Q1") (pin "2") (pinfunction "S_2") (pintype "passive"))
      (node (ref "R10") (pin "1") (pinfunction "1_1") (pintype "passive"))
    )
    (net (code "52") (name "VDD") (class "Default")
      (node (ref "C15") (pin "2") (pinfunction "2_2") (pintype "passive"))
      (node (ref "C16") (pin "2") (pinfunction "2_2") (pintype "passive"))
      (node (ref "MICL") (pin "5") (pinfunction "VDD_5") (pintype "power_in"))
      (node (ref "MICR") (pin "2") (pinfunction "L/R_2") (pintype "passive"))
      (node (ref "MICR") (pin "5") (pinfunction "VDD_5") (pintype "power_in"))
    )
    (net (code "53") (name "VDD_3V3") (class "Default")
      (node (ref "C34") (pin "2") (pinfunction "2_2") (pintype "passive"))
      (node (ref "C42") (pin "2") (pinfunction "2_2") (pintype "passive"))
      (node (ref "C43") (pin "2") (pinfunction "2_2") (pintype "passive"))
      (node (ref "U4") (pin "F8") (pinfunction "CODEC_VDD_F8") (pintype "passive"))
      (node (ref "U5") (pin "1") (pinfunction "OUT_1") (pintype "passive"))
    )
    (net (code "54") (name "VDD_CORE11") (class "Default")
      (node (ref "C35") (pin "2") (pinfunction "2_2") (pintype "passive"))
      (node (ref "L9") (pin "2") (pinfunction "2_2") (pintype "passive"))
      (node (ref "U4") (pin "F2") (pinfunction "VDD_CORE11_F2") (pintype "passive"))
      (node (ref "U4") (pin "F7") (pinfunction "VDD_CORE11_F7") (pintype "passive"))
      (node (ref "U4") (pin "G1") (pinfunction "VSENSE-RAR_G1") (pintype "passive"))
    )
    (net (code "55") (name "VDD_IO33") (class "Default")
      (node (ref "C37") (pin "2") (pinfunction "2_2") (pintype "passive"))
      (node (ref "U4") (pin "E3") (pinfunction "ILR_VOUT_IO33_E3") (pintype "passive"))
      (node (ref "U5") (pin "3") (pinfunction "EN_3") (pintype "passive"))
    )
    (net (code "56") (name "VDD_IP33") (class "Default")
      (node (ref "C38") (pin "2") (pinfunction "2_2") (pintype "passive"))
      (node (ref "C55") (pin "2") (pinfunction "2_2") (pintype "passive"))
      (node (ref "C6") (pin "2") (pinfunction "2_2") (pintype "passive"))
      (node (ref "C60") (pin "2") (pinfunction "2_2") (pintype "passive"))
      (node (ref "C7") (pin "2") (pinfunction "2_2") (pintype "passive"))
      (node (ref "DMIC1") (pin "1") (pinfunction "Power_1") (pintype "passive"))
      (node (ref "DMIC2") (pin "1") (pinfunction "Power_1") (pintype "passive"))
      (node (ref "DMIC2") (pin "5") (pinfunction "L/R_5") (pintype "passive"))
      (node (ref "ESD1") (pin "1") (pinfunction "1_1") (pintype "passive"))
      (node (ref "ESD2") (pin "1") (pinfunction "1_1") (pintype "passive"))
      (node (ref "R14") (pin "2") (pinfunction "2_2") (pintype "passive"))
      (node (ref "TP22") (pin "1") (pinfunction "1_1") (pintype "passive"))
      (node (ref "TP29") (pin "1") (pinfunction "1_1") (pintype "passive"))
      (node (ref "TP31") (pin "1") (pinfunction "1_1") (pintype "passive"))
      (node (ref "U4") (pin "D3") (pinfunction "ILR_VOUT_IP33_D3") (pintype "passive"))
    )
    (net (code "57") (name "unconnected-(U4-AIN1-PadA9)") (class "Default")
      (node (ref "U4") (pin "A9") (pinfunction "AIN1_A9") (pintype "passive"))
    )
    (net (code "58") (name "unconnected-(U4-AIN2-PadB9)") (class "Default")
      (node (ref "U4") (pin "B9") (pinfunction "AIN2_B9") (pintype "passive"))
    )
    (net (code "59") (name "unconnected-(U4-AIP1-PadA8)") (class "Default")
      (node (ref "U4") (pin "A8") (pinfunction "AIP1_A8") (pintype "passive"))
    )
    (net (code "60") (name "unconnected-(U4-AIP2-PadC9)") (class "Default")
      (node (ref "U4") (pin "C9") (pinfunction "AIP2_C9") (pintype "passive"))
    )
    (net (code "61") (name "unconnected-(U4-DMIC_CLK11(GPIO_DAT8)-PadA7)") (class "Default")
      (node (ref "U4") (pin "A7") (pinfunction "DMIC_CLK11(GPIO_DAT8)_A7") (pintype "passive"))
    )
    (net (code "62") (name "unconnected-(U4-DMIC_IN1{slash}_(GPIO_DAT9)-PadB8)") (class "Default")
      (node (ref "U4") (pin "B8") (pinfunction "DMIC_IN1/_(GPIO_DAT9)_B8") (pintype "passive"))
    )
    (net (code "63") (name "unconnected-(U4-EFUSE_VDDQ-PadF6)") (class "Default")
      (node (ref "U4") (pin "F6") (pinfunction "EFUSE_VDDQ_F6") (pintype "passive"))
    )
    (net (code "64") (name "unconnected-(U4-GPIOAO_DAT0-PadF5)") (class "Default")
      (node (ref "U4") (pin "F5") (pinfunction "GPIOAO_DAT0_F5") (pintype "passive"))
    )
    (net (code "65") (name "unconnected-(U4-GPIO_DAT0{slash}I2S1_CLK-PadB3)") (class "Default")
      (node (ref "U4") (pin "B3") (pinfunction "GPIO_DAT0/I2S1_CLK_B3") (pintype "passive"))
    )
    (net (code "66") (name "unconnected-(U4-GPIO_DAT1_{slash}I2S1_WS-PadB4)") (class "Default")
      (node (ref "U4") (pin "B4") (pinfunction "GPIO_DAT1_/I2S1_WS_B4") (pintype "passive"))
    )
    (net (code "67") (name "unconnected-(U4-GPIO_DAT2{slash}I2S1_SDI-PadA4)") (class "Default")
      (node (ref "U4") (pin "A4") (pinfunction "GPIO_DAT2/I2S1_SDI_A4") (pintype "passive"))
    )
    (net (code "68") (name "unconnected-(U4-GPIO_DAT3{slash}I2S1_SDO-PadB5)") (class "Default")
      (node (ref "U4") (pin "B5") (pinfunction "GPIO_DAT3/I2S1_SDO_B5") (pintype "passive"))
    )
    (net (code "69") (name "unconnected-(U4-GPIO_DAT10{slash}I2C2_CLK-PadD2)") (class "Default")
      (node (ref "U4") (pin "D2") (pinfunction "GPIO_DAT10/I2C2_CLK_D2") (pintype "passive"))
    )
    (net (code "70") (name "unconnected-(U4-GPIO_DAT11{slash}I2C2_SDA-PadC2)") (class "Default")
      (node (ref "U4") (pin "C2") (pinfunction "GPIO_DAT11/I2C2_SDA_C2") (pintype "passive"))
    )
    (net (code "71") (name "unconnected-(U4-MIC_BIAS1-PadC8)") (class "Default")
      (node (ref "U4") (pin "C8") (pinfunction "MIC_BIAS1_C8") (pintype "passive"))
    )
    (net (code "72") (name "unconnected-(U4-NC(TXRTUNE)-PadE2)") (class "Default")
      (node (ref "U4") (pin "E2") (pinfunction "NC(TXRTUNE)_E2") (pintype "passive"))
    )
    (net (code "73") (name "unconnected-(U4-RST_N(MIC_BIAS2)-PadD8)") (class "Default")
      (node (ref "U4") (pin "D8") (pinfunction "RST_N(MIC_BIAS2)_D8") (pintype "passive"))
    )
  )
)
